# HBridgeInterface.net
KiCad netlist of a schematic drawn in Altium Designer
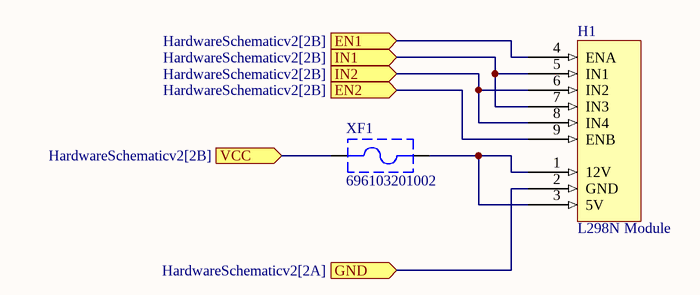
[diagram p0: HBridgeInterface.SchDoc]

(export (version "E")
  (design (tool "Eeschema 10.0.6"))
  (components
    (comp (ref "H1")
      (value "L298N Module")
      (footprint "New footprint 1")
      (description "Direct conector for H-Bridge")
      (libsource (lib "University of Auckland") (part "L298N Module-Symbol-1"))
    )
    (comp (ref "XF1")
      (value "696103201002")
      (footprint "696103201002")
      (libsource (lib "Altium Content Vault") (part "Fuse Holder"))
    )
  )
  (nets
    (net (code "1") (name "/EN1") (class "Default")
      (node (ref "H1") (pin "4") (pinfunction "ENA_4") (pintype "input"))
    )
    (net (code "2") (name "/EN2") (class "Default")
      (node (ref "H1") (pin "9") (pinfunction "ENB_9") (pintype "input"))
    )
    (net (code "3") (name "/GND") (class "Default")
      (node (ref "H1") (pin "2") (pinfunction "GND_2") (pintype "input"))
    )
    (net (code "4") (name "/IN1") (class "Default")
      (node (ref "H1") (pin "5") (pinfunction "IN1_5") (pintype "input"))
      (node (ref "H1") (pin "7") (pinfunction "IN3_7") (pintype "input"))
    )
    (net (code "5") (name "/IN2") (class "Default")
      (node (ref "H1") (pin "6") (pinfunction "IN2_6") (pintype "input"))
      (node (ref "H1") (pin "8") (pinfunction "IN4_8") (pintype "input"))
    )
    (net (code "6") (name "/VCC") (class "Default")
      (node (ref "XF1") (pin "1") (pinfunction "1_1") (pintype "passive"))
    )
    (net (code "7") (name "Net-(H1-12V)") (class "Default")
      (node (ref "H1") (pin "1") (pinfunction "12V_1") (pintype "input"))
      (node (ref "H1") (pin "3") (pinfunction "5V_3") (pintype "input"))
      (node (ref "XF1") (pin "2") (pinfunction "2_2") (pintype "passive"))
    )
  )
)
